# CHIP_dispv1_0.net
KiCad netlist of a schematic drawn in EAGLE
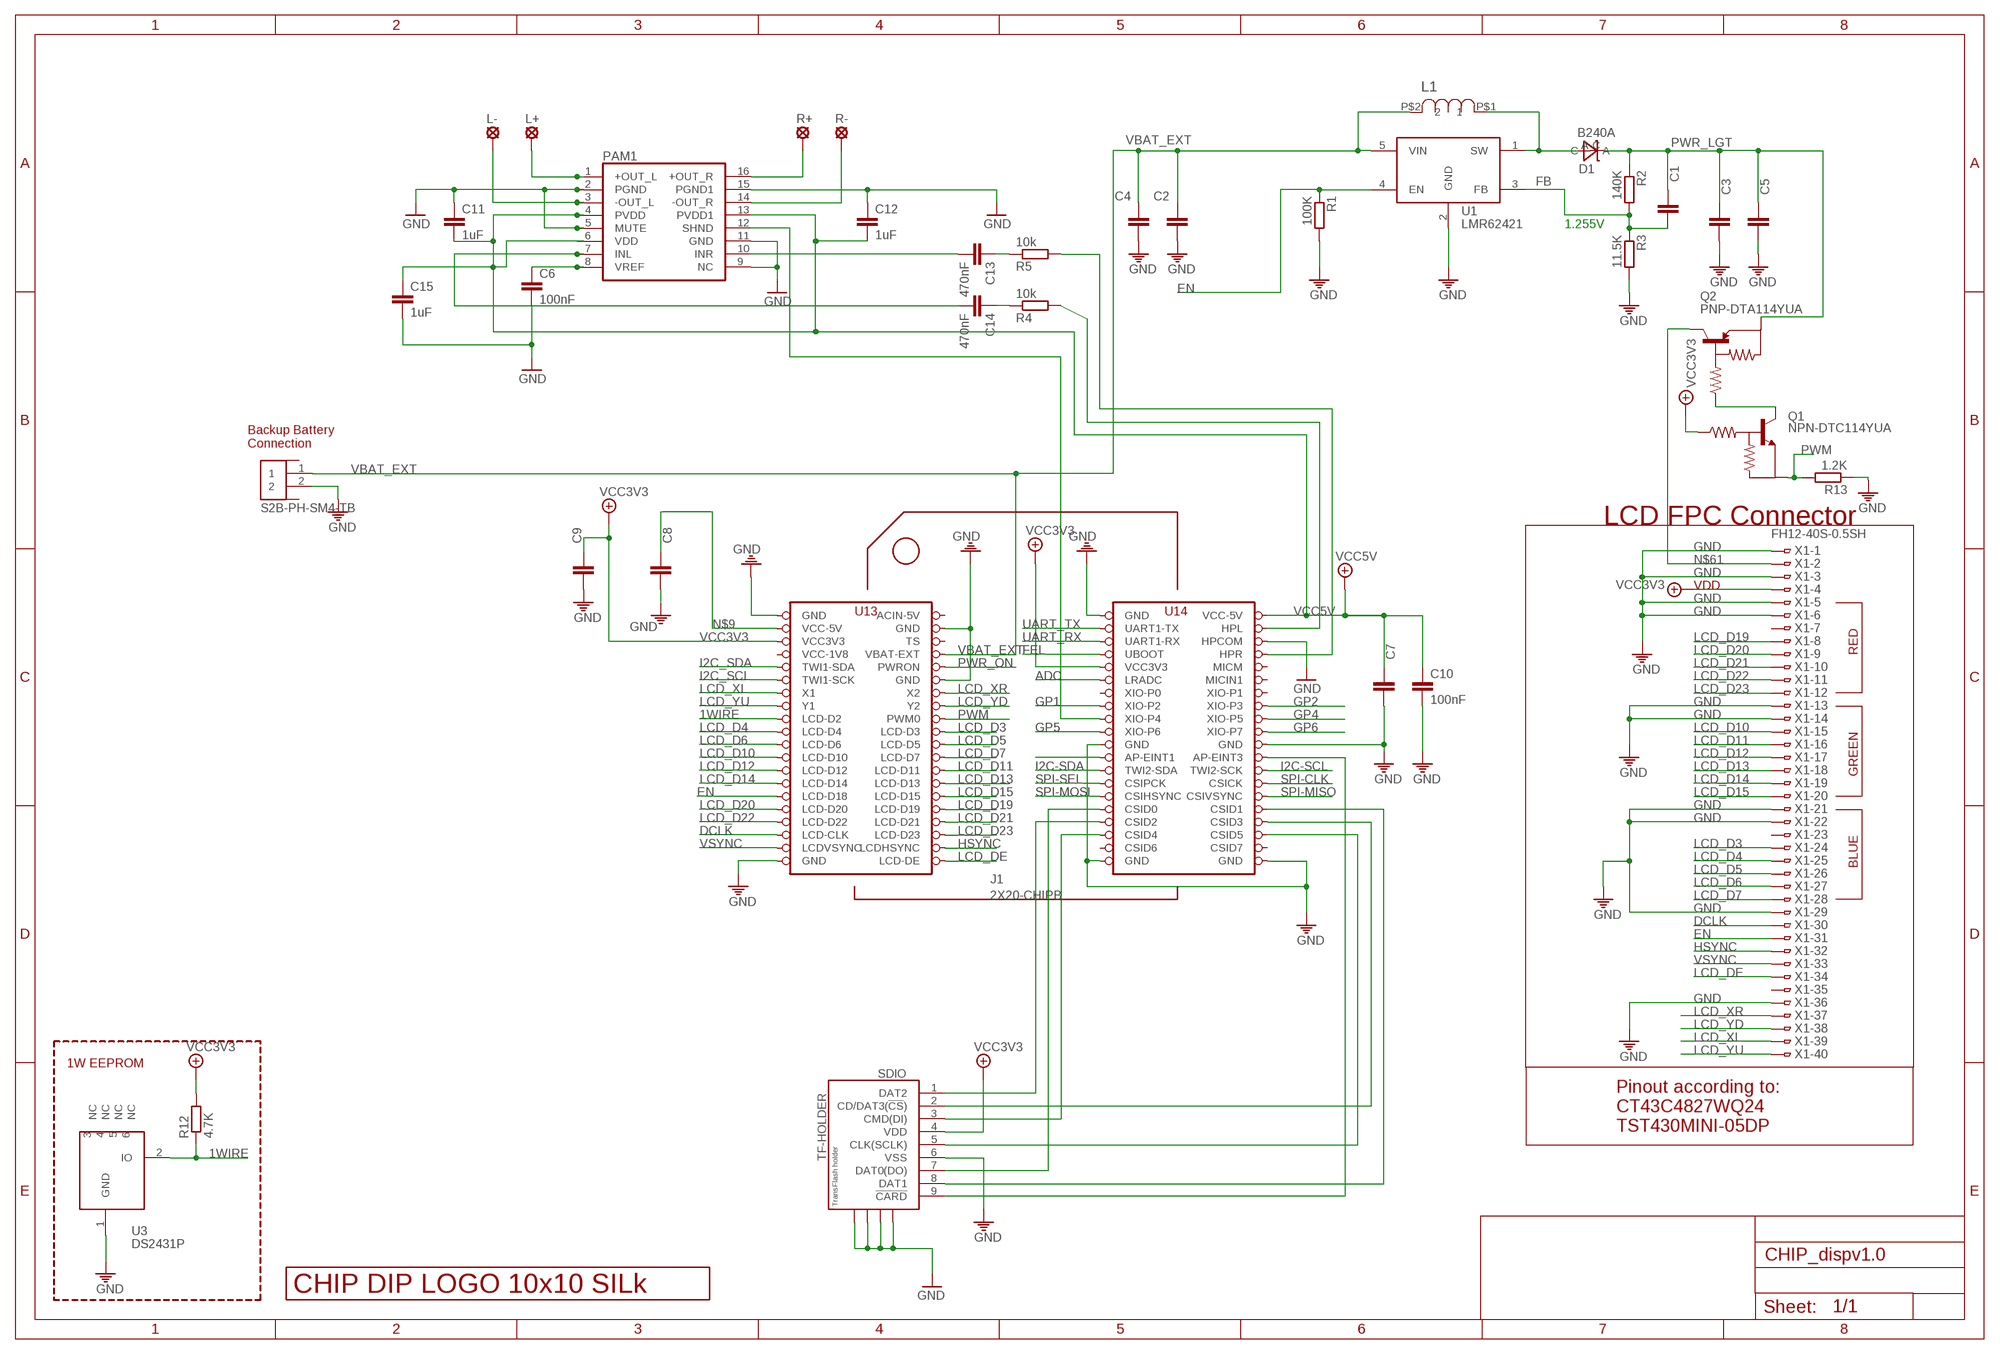
[diagram p0: schematic, sheet 1]

(export (version "E")
  (design (tool "Eeschema 10.0.6"))
  (components
    (comp (ref "C1")
      (value "220pF")
      (footprint "eagle-import:C0805")
      (libsource (lib "eagle-import") (part "C-EUC0805"))
    )
    (comp (ref "C2")
      (value "100nF")
      (footprint "eagle-import:C0805")
      (libsource (lib "eagle-import") (part "C-EUC0805"))
    )
    (comp (ref "C3")
      (value "100nF")
      (footprint "eagle-import:C0805")
      (libsource (lib "eagle-import") (part "C-EUC0805"))
    )
    (comp (ref "C4")
      (value "22uF")
      (footprint "eagle-import:C0805")
      (libsource (lib "eagle-import") (part "C-EUC0805"))
    )
    (comp (ref "C5")
      (value "22uF")
      (footprint "eagle-import:C0805")
      (libsource (lib "eagle-import") (part "C-EUC0805"))
    )
    (comp (ref "C6")
      (value "100nF")
      (footprint "eagle-import:C0805")
      (libsource (lib "eagle-import") (part "C-EUC0805"))
    )
    (comp (ref "C7")
      (value "22uF")
      (footprint "eagle-import:C0805")
      (libsource (lib "eagle-import") (part "C-EUC0805"))
    )
    (comp (ref "C8")
      (value "100nF")
      (footprint "eagle-import:C0805")
      (libsource (lib "eagle-import") (part "C-EUC0805"))
    )
    (comp (ref "C9")
      (value "100nF")
      (footprint "eagle-import:C0805")
      (libsource (lib "eagle-import") (part "C-EUC0805"))
    )
    (comp (ref "C10")
      (value "100nF")
      (footprint "eagle-import:C0805")
      (libsource (lib "eagle-import") (part "C-EUC0805"))
    )
    (comp (ref "C11")
      (value "1uF")
      (footprint "eagle-import:C0805")
      (libsource (lib "eagle-import") (part "C-EUC0805"))
    )
    (comp (ref "C12")
      (value "1uF")
      (footprint "eagle-import:C0805")
      (libsource (lib "eagle-import") (part "C-EUC0805"))
    )
    (comp (ref "C13")
      (value "470nF")
      (footprint "eagle-import:C0805")
      (libsource (lib "eagle-import") (part "C-EUC0805"))
    )
    (comp (ref "C14")
      (value "470nF")
      (footprint "eagle-import:C0805")
      (libsource (lib "eagle-import") (part "C-EUC0805"))
    )
    (comp (ref "C15")
      (value "1uF")
      (footprint "eagle-import:C0805")
      (libsource (lib "eagle-import") (part "C-EUC0805"))
    )
    (comp (ref "D1")
      (value "B240A")
      (footprint "eagle-import:DO-214AC")
      (fields (field (name "MFG") "DIGIKEY") (field (name "VENDOR_PART_NUMBER") "B240A-13-F"))
      (libsource (lib "eagle-import") (part "DIODE_SCHTKY_B240"))
    )
    (comp (ref "J1")
      (value "2X20-CHIPB")
      (footprint "eagle-import:2X20CHIP_SM")
      (libsource (lib "eagle-import") (part "2X20-CHIPB"))
    )
    (comp (ref "J3")
      (value "S2B-PH-SM4-TB")
      (footprint "eagle-import:S2B-PH-SM4-TB")
      (fields (field (name "MFG") "DIGIKEY") (field (name "VENDOR_PART_NUMBER") "S2B-PH-SM4-TB(LF)(SN)"))
      (libsource (lib "eagle-import") (part "S2B-PH-SM4-TB"))
    )
    (comp (ref "L+")
      (value "SE11")
      (footprint "eagle-import:SE11")
      (libsource (lib "eagle-import") (part "SE11"))
    )
    (comp (ref "L-")
      (value "SE11")
      (footprint "eagle-import:SE11")
      (libsource (lib "eagle-import") (part "SE11"))
    )
    (comp (ref "L1")
      (value "SRN6045-100M")
      (footprint "eagle-import:SRN6045")
      (fields (field (name "MFG") "DIGIKEY"))
      (libsource (lib "eagle-import") (part "SRN6045-100M"))
    )
    (comp (ref "PAM1")
      (value "PAM8403")
      (footprint "eagle-import:SOP-16")
      (libsource (lib "eagle-import") (part "PAM8403"))
    )
    (comp (ref "Q1")
      (value "NPN-DTC114YUA")
      (footprint "eagle-import:SOT323")
      (libsource (lib "eagle-import") (part "NPN-DTC114YUA"))
    )
    (comp (ref "Q2")
      (value "PNP-DTA114YUA")
      (footprint "eagle-import:SOT323")
      (libsource (lib "eagle-import") (part "PNP-DTA114YUA"))
    )
    (comp (ref "R+")
      (value "SE11")
      (footprint "eagle-import:SE11")
      (libsource (lib "eagle-import") (part "SE11"))
    )
    (comp (ref "R-")
      (value "SE11")
      (footprint "eagle-import:SE11")
      (libsource (lib "eagle-import") (part "SE11"))
    )
    (comp (ref "R1")
      (value "100K")
      (footprint "eagle-import:M0805")
      (libsource (lib "eagle-import") (part "R-EU_M0805"))
    )
    (comp (ref "R2")
      (value "140K")
      (footprint "eagle-import:M0805")
      (libsource (lib "eagle-import") (part "R-EU_M0805"))
    )
    (comp (ref "R3")
      (value "11.5K")
      (footprint "eagle-import:M0805")
      (libsource (lib "eagle-import") (part "R-EU_M0805"))
    )
    (comp (ref "R4")
      (value "10k")
      (footprint "eagle-import:R0805")
      (libsource (lib "eagle-import") (part "R-EU_R0805"))
    )
    (comp (ref "R5")
      (value "10k")
      (footprint "eagle-import:R0805")
      (libsource (lib "eagle-import") (part "R-EU_R0805"))
    )
    (comp (ref "R12")
      (value "4.7K")
      (footprint "eagle-import:M0805")
      (libsource (lib "eagle-import") (part "R-EU_M0805"))
    )
    (comp (ref "R13")
      (value "1.2K")
      (footprint "eagle-import:M0805")
      (libsource (lib "eagle-import") (part "R-EU_M0805"))
    )
    (comp (ref "SDIO")
      (value "TF-HOLDER")
      (footprint "eagle-import:TF-PULL")
      (libsource (lib "eagle-import") (part "TF-HOLDER"))
    )
    (comp (ref "U$2")
      (value "LOGO_10X10_SILK")
      (footprint "eagle-import:LOGO2_10X10_SILK")
      (libsource (lib "eagle-import") (part "LOGO_10X10_SILK"))
    )
    (comp (ref "U1")
      (value "LMR62421")
      (footprint "eagle-import:SOT23-5")
      (fields (field (name "MFG") "DIGIKEY") (field (name "VENDOR_PART_NUMBER") "LMR62421XMFE/NOPB"))
      (libsource (lib "eagle-import") (part "LMR62421"))
    )
    (comp (ref "U3")
      (value "DS2431P")
      (footprint "eagle-import:TSOC6")
      (fields (field (name "MFG") "DIGIKEY") (field (name "VENDOR_PART_NUMBER") "DS2431P+T&R"))
      (libsource (lib "eagle-import") (part "DS2431P"))
    )
    (comp (ref "X1")
      (value "FH12-40S-0.5SH")
      (footprint "eagle-import:FH12-40S-0.5SH")
      (fields (field (name "MFG") "DIGIKEY") (field (name "VENDOR_PART_NUMBER") "FH12-40S-0.5SH(55)"))
      (libsource (lib "eagle-import") (part "FH12-40S-0.5SH"))
    )
  )
  (nets
    (net (code "1") (name "/1WIRE") (class "Default")
      (node (ref "J1") (pin "LCD-D2") (pinfunction "LCD-D2_LCD-D2") (pintype "passive"))
      (node (ref "R12") (pin "1") (pinfunction "1_1") (pintype "passive"))
      (node (ref "U3") (pin "2") (pinfunction "IO_2") (pintype "bidirectional"))
    )
    (net (code "2") (name "/ADC") (class "Default")
      (node (ref "J1") (pin "LRADC") (pinfunction "LRADC_LRADC") (pintype "passive"))
    )
    (net (code "3") (name "/DCLK") (class "Default")
      (node (ref "J1") (pin "LCD-CLK") (pinfunction "LCD-CLK_LCD-CLK") (pintype "passive"))
      (node (ref "X1") (pin "30") (pinfunction "1_30") (pintype "passive"))
    )
    (net (code "4") (name "/EN") (class "Default")
      (node (ref "J1") (pin "LCD-D18") (pinfunction "LCD-D18_LCD-D18") (pintype "passive"))
      (node (ref "R1") (pin "1") (pinfunction "1_1") (pintype "passive"))
      (node (ref "U1") (pin "4") (pinfunction "EN_4") (pintype "bidirectional"))
      (node (ref "X1") (pin "31") (pinfunction "1_31") (pintype "passive"))
    )
    (net (code "5") (name "/FB") (class "Default")
      (node (ref "C1") (pin "2") (pinfunction "2_2") (pintype "passive"))
      (node (ref "R2") (pin "2") (pinfunction "2_2") (pintype "passive"))
      (node (ref "R3") (pin "1") (pinfunction "1_1") (pintype "passive"))
      (node (ref "U1") (pin "3") (pinfunction "FB_3") (pintype "bidirectional"))
    )
    (net (code "6") (name "/FEL") (class "Default")
      (node (ref "J1") (pin "FEL") (pinfunction "UBOOT_FEL") (pintype "passive"))
    )
    (net (code "7") (name "/GP1") (class "Default")
      (node (ref "J1") (pin "XIO-P2") (pinfunction "XIO-P2_XIO-P2") (pintype "passive"))
    )
    (net (code "8") (name "/GP2") (class "Default")
      (node (ref "J1") (pin "XIO-P3") (pinfunction "XIO-P3_XIO-P3") (pintype "passive"))
    )
    (net (code "9") (name "/GP4") (class "Default")
      (node (ref "J1") (pin "XIO-P5") (pinfunction "XIO-P5_XIO-P5") (pintype "passive"))
    )
    (net (code "10") (name "/GP5") (class "Default")
      (node (ref "J1") (pin "XIO-P6") (pinfunction "XIO-P6_XIO-P6") (pintype "passive"))
    )
    (net (code "11") (name "/GP6") (class "Default")
      (node (ref "J1") (pin "XIO-P7") (pinfunction "XIO-P7_XIO-P7") (pintype "passive"))
    )
    (net (code "12") (name "/HSYNC") (class "Default")
      (node (ref "J1") (pin "LCD-HSYNC") (pinfunction "LCDHSYNC_LCD-HSYNC") (pintype "passive"))
      (node (ref "X1") (pin "32") (pinfunction "1_32") (pintype "passive"))
    )
    (net (code "13") (name "/I2C-SCL") (class "Default")
      (node (ref "J1") (pin "TWI2-SCK") (pinfunction "TWI2-SCK_TWI2-SCK") (pintype "passive"))
    )
    (net (code "14") (name "/I2C-SDA") (class "Default")
      (node (ref "J1") (pin "TWI2-SDA") (pinfunction "TWI2-SDA_TWI2-SDA") (pintype "passive"))
    )
    (net (code "15") (name "/I2C_SCL") (class "Default")
      (node (ref "J1") (pin "TWI1-SCK") (pinfunction "TWI1-SCK_TWI1-SCK") (pintype "passive"))
    )
    (net (code "16") (name "/I2C_SDA") (class "Default")
      (node (ref "J1") (pin "TWI1-SDA") (pinfunction "TWI1-SDA_TWI1-SDA") (pintype "passive"))
    )
    (net (code "17") (name "/LCD_D3") (class "Default")
      (node (ref "J1") (pin "LCD-D3") (pinfunction "LCD-D3_LCD-D3") (pintype "passive"))
      (node (ref "X1") (pin "24") (pinfunction "1_24") (pintype "passive"))
    )
    (net (code "18") (name "/LCD_D4") (class "Default")
      (node (ref "J1") (pin "LCD-D4") (pinfunction "LCD-D4_LCD-D4") (pintype "passive"))
      (node (ref "X1") (pin "25") (pinfunction "1_25") (pintype "passive"))
    )
    (net (code "19") (name "/LCD_D5") (class "Default")
      (node (ref "J1") (pin "LCD-D5") (pinfunction "LCD-D5_LCD-D5") (pintype "passive"))
      (node (ref "X1") (pin "26") (pinfunction "1_26") (pintype "passive"))
    )
    (net (code "20") (name "/LCD_D6") (class "Default")
      (node (ref "J1") (pin "LCD-D6") (pinfunction "LCD-D6_LCD-D6") (pintype "passive"))
      (node (ref "X1") (pin "27") (pinfunction "1_27") (pintype "passive"))
    )
    (net (code "21") (name "/LCD_D7") (class "Default")
      (node (ref "J1") (pin "LCD-D7") (pinfunction "LCD-D7_LCD-D7") (pintype "passive"))
      (node (ref "X1") (pin "28") (pinfunction "1_28") (pintype "passive"))
    )
    (net (code "22") (name "/LCD_D10") (class "Default")
      (node (ref "J1") (pin "LCD-D10") (pinfunction "LCD-D10_LCD-D10") (pintype "passive"))
      (node (ref "X1") (pin "15") (pinfunction "1_15") (pintype "passive"))
    )
    (net (code "23") (name "/LCD_D11") (class "Default")
      (node (ref "J1") (pin "LCD-D11") (pinfunction "LCD-D11_LCD-D11") (pintype "passive"))
      (node (ref "X1") (pin "16") (pinfunction "1_16") (pintype "passive"))
    )
    (net (code "24") (name "/LCD_D12") (class "Default")
      (node (ref "J1") (pin "LCD-D12") (pinfunction "LCD-D12_LCD-D12") (pintype "passive"))
      (node (ref "X1") (pin "17") (pinfunction "1_17") (pintype "passive"))
    )
    (net (code "25") (name "/LCD_D13") (class "Default")
      (node (ref "J1") (pin "LCD-D13") (pinfunction "LCD-D13_LCD-D13") (pintype "passive"))
      (node (ref "X1") (pin "18") (pinfunction "1_18") (pintype "passive"))
    )
    (net (code "26") (name "/LCD_D14") (class "Default")
      (node (ref "J1") (pin "LCD-D14") (pinfunction "LCD-D14_LCD-D14") (pintype "passive"))
      (node (ref "X1") (pin "19") (pinfunction "1_19") (pintype "passive"))
    )
    (net (code "27") (name "/LCD_D15") (class "Default")
      (node (ref "J1") (pin "LCD-D15") (pinfunction "LCD-D15_LCD-D15") (pintype "passive"))
      (node (ref "X1") (pin "20") (pinfunction "1_20") (pintype "passive"))
    )
    (net (code "28") (name "/LCD_D19") (class "Default")
      (node (ref "J1") (pin "LCD-D19") (pinfunction "LCD-D19_LCD-D19") (pintype "passive"))
      (node (ref "X1") (pin "8") (pinfunction "1_8") (pintype "passive"))
    )
    (net (code "29") (name "/LCD_D20") (class "Default")
      (node (ref "J1") (pin "LCD-D20") (pinfunction "LCD-D20_LCD-D20") (pintype "passive"))
      (node (ref "X1") (pin "9") (pinfunction "1_9") (pintype "passive"))
    )
    (net (code "30") (name "/LCD_D21") (class "Default")
      (node (ref "J1") (pin "LCD-D21") (pinfunction "LCD-D21_LCD-D21") (pintype "passive"))
      (node (ref "X1") (pin "10") (pinfunction "1_10") (pintype "passive"))
    )
    (net (code "31") (name "/LCD_D22") (class "Default")
      (node (ref "J1") (pin "LCD-D22") (pinfunction "LCD-D22_LCD-D22") (pintype "passive"))
      (node (ref "X1") (pin "11") (pinfunction "1_11") (pintype "passive"))
    )
    (net (code "32") (name "/LCD_D23") (class "Default")
      (node (ref "J1") (pin "LCD-D23") (pinfunction "LCD-D23_LCD-D23") (pintype "passive"))
      (node (ref "X1") (pin "12") (pinfunction "1_12") (pintype "passive"))
    )
    (net (code "33") (name "/LCD_DE") (class "Default")
      (node (ref "J1") (pin "LCD-DE") (pinfunction "LCD-DE_LCD-DE") (pintype "passive"))
      (node (ref "X1") (pin "34") (pinfunction "1_34") (pintype "passive"))
    )
    (net (code "34") (name "/LCD_XL") (class "Default")
      (node (ref "J1") (pin "X1") (pinfunction "X1_X1") (pintype "passive"))
      (node (ref "X1") (pin "39") (pinfunction "1_39") (pintype "passive"))
    )
    (net (code "35") (name "/LCD_XR") (class "Default")
      (node (ref "J1") (pin "X2") (pinfunction "X2_X2") (pintype "passive"))
      (node (ref "X1") (pin "37") (pinfunction "1_37") (pintype "passive"))
    )
    (net (code "36") (name "/LCD_YD") (class "Default")
      (node (ref "J1") (pin "Y2") (pinfunction "Y2_Y2") (pintype "passive"))
      (node (ref "X1") (pin "38") (pinfunction "1_38") (pintype "passive"))
    )
    (net (code "37") (name "/LCD_YU") (class "Default")
      (node (ref "J1") (pin "Y1") (pinfunction "Y1_Y1") (pintype "passive"))
      (node (ref "X1") (pin "40") (pinfunction "1_40") (pintype "passive"))
    )
    (net (code "38") (name "/N$9") (class "Default")
      (node (ref "C8") (pin "1") (pinfunction "1_1") (pintype "passive"))
      (node (ref "J1") (pin "VCC5V@0") (pinfunction "VCC-5V_VCC5V@0") (pintype "power_in"))
    )
    (net (code "39") (name "/N$61") (class "Default")
      (node (ref "Q2") (pin "3") (pinfunction "OUT_3") (pintype "passive"))
      (node (ref "X1") (pin "2") (pinfunction "1_2") (pintype "passive"))
    )
    (net (code "40") (name "/PWM") (class "Default")
      (node (ref "J1") (pin "PWM0") (pinfunction "PWM0_PWM0") (pintype "passive"))
      (node (ref "Q1") (pin "2") (pinfunction "GND_2") (pintype "passive"))
      (node (ref "R13") (pin "2") (pinfunction "2_2") (pintype "passive"))
    )
    (net (code "41") (name "/PWR_LGT") (class "Default")
      (node (ref "C1") (pin "1") (pinfunction "1_1") (pintype "passive"))
      (node (ref "C3") (pin "1") (pinfunction "1_1") (pintype "passive"))
      (node (ref "C5") (pin "1") (pinfunction "1_1") (pintype "passive"))
      (node (ref "D1") (pin "C") (pinfunction "C_C") (pintype "bidirectional"))
      (node (ref "Q2") (pin "2") (pinfunction "GND_2") (pintype "passive"))
      (node (ref "R2") (pin "1") (pinfunction "1_1") (pintype "passive"))
    )
    (net (code "42") (name "/PWR_ON") (class "Default")
      (node (ref "J1") (pin "PWRON") (pinfunction "PWRON_PWRON") (pintype "passive"))
    )
    (net (code "43") (name "/SPI-CLK") (class "Default")
      (node (ref "J1") (pin "CSICK") (pinfunction "CSICK_CSICK") (pintype "passive"))
    )
    (net (code "44") (name "/SPI-MISO") (class "Default")
      (node (ref "J1") (pin "CSIVSYNC") (pinfunction "CSIVSYNC_CSIVSYNC") (pintype "passive"))
    )
    (net (code "45") (name "/SPI-MOSI") (class "Default")
      (node (ref "J1") (pin "CSIHSYNC") (pinfunction "CSIHSYNC_CSIHSYNC") (pintype "passive"))
    )
    (net (code "46") (name "/SPI-SEL") (class "Default")
      (node (ref "J1") (pin "CSIPCK") (pinfunction "CSIPCK_CSIPCK") (pintype "passive"))
    )
    (net (code "47") (name "/UART_RX") (class "Default")
      (node (ref "J1") (pin "UART1-RX") (pinfunction "UART1-RX_UART1-RX") (pintype "passive"))
    )
    (net (code "48") (name "/UART_TX") (class "Default")
      (node (ref "J1") (pin "UART1-TX") (pinfunction "UART1-TX_UART1-TX") (pintype "passive"))
    )
    (net (code "49") (name "/VBAT_EXT") (class "Default")
      (node (ref "C2") (pin "1") (pinfunction "1_1") (pintype "passive"))
      (node (ref "C4") (pin "1") (pinfunction "1_1") (pintype "passive"))
      (node (ref "J1") (pin "BAT") (pinfunction "VBAT-EXT_BAT") (pintype "passive"))
      (node (ref "J3") (pin "1") (pinfunction "1_1") (pintype "bidirectional"))
      (node (ref "L1") (pin "P$2") (pinfunction "2_P$2") (pintype "passive"))
      (node (ref "U1") (pin "5") (pinfunction "VIN_5") (pintype "bidirectional"))
    )
    (net (code "50") (name "/VCC-1V8") (class "Default")
      (node (ref "J1") (pin "VCC1V8") (pinfunction "VCC-1V8_VCC1V8") (pintype "power_in"))
    )
    (net (code "51") (name "/VSYNC") (class "Default")
      (node (ref "J1") (pin "LCD-VSYNC") (pinfunction "LCDVSYNC_LCD-VSYNC") (pintype "passive"))
      (node (ref "X1") (pin "33") (pinfunction "1_33") (pintype "passive"))
    )
    (net (code "52") (name "GND") (class "Default")
      (node (ref "C10") (pin "2") (pinfunction "2_2") (pintype "passive"))
      (node (ref "C11") (pin "1") (pinfunction "1_1") (pintype "passive"))
      (node (ref "C12") (pin "1") (pinfunction "1_1") (pintype "passive"))
      (node (ref "C15") (pin "2") (pinfunction "2_2") (pintype "passive"))
      (node (ref "C2") (pin "2") (pinfunction "2_2") (pintype "passive"))
      (node (ref "C3") (pin "2") (pinfunction "2_2") (pintype "passive"))
      (node (ref "C4") (pin "2") (pinfunction "2_2") (pintype "passive"))
      (node (ref "C5") (pin "2") (pinfunction "2_2") (pintype "passive"))
      (node (ref "C6") (pin "2") (pinfunction "2_2") (pintype "passive"))
      (node (ref "C7") (pin "2") (pinfunction "2_2") (pintype "passive"))
      (node (ref "C8") (pin "2") (pinfunction "2_2") (pintype "passive"))
      (node (ref "C9") (pin "2") (pinfunction "2_2") (pintype "passive"))
      (node (ref "J1") (pin "GND@1") (pinfunction "GND_GND@1") (pintype "power_in"))
      (node (ref "J1") (pin "GND@10") (pinfunction "GND_GND@10") (pintype "power_in"))
      (node (ref "J1") (pin "GND@2") (pinfunction "GND_GND@2") (pintype "power_in"))
      (node (ref "J1") (pin "GND@3") (pinfunction "GND_GND@3") (pintype "power_in"))
      (node (ref "J1") (pin "GND@4") (pinfunction "GND_GND@4") (pintype "power_in"))
      (node (ref "J1") (pin "GND@5") (pinfunction "GND_GND@5") (pintype "power_in"))
      (node (ref "J1") (pin "GND@6") (pinfunction "GND_GND@6") (pintype "power_in"))
      (node (ref "J1") (pin "GND@7") (pinfunction "GND_GND@7") (pintype "power_in"))
      (node (ref "J1") (pin "GND@8") (pinfunction "GND_GND@8") (pintype "power_in"))
      (node (ref "J1") (pin "HPCOM") (pinfunction "HPCOM_HPCOM") (pintype "passive"))
      (node (ref "J3") (pin "2") (pinfunction "2_2") (pintype "bidirectional"))
      (node (ref "PAM1") (pin "11") (pinfunction "GND_11") (pintype "output"))
      (node (ref "PAM1") (pin "15") (pinfunction "PGND1_15") (pintype "output"))
      (node (ref "PAM1") (pin "2") (pinfunction "PGND_2") (pintype "input"))
      (node (ref "PAM1") (pin "5") (pinfunction "MUTE_5") (pintype "input"))
      (node (ref "PAM1") (pin "9") (pinfunction "NC_9") (pintype "output"))
      (node (ref "R1") (pin "2") (pinfunction "2_2") (pintype "passive"))
      (node (ref "R13") (pin "1") (pinfunction "1_1") (pintype "passive"))
      (node (ref "R3") (pin "2") (pinfunction "2_2") (pintype "passive"))
      (node (ref "SDIO") (pin "6") (pinfunction "VSS_6") (pintype "power_in"))
      (node (ref "SDIO") (pin "S1") (pinfunction "S1_S1") (pintype "passive"))
      (node (ref "SDIO") (pin "S2") (pinfunction "S2_S2") (pintype "passive"))
      (node (ref "SDIO") (pin "S3") (pinfunction "S3_S3") (pintype "passive"))
      (node (ref "SDIO") (pin "S4") (pinfunction "S4_S4") (pintype "passive"))
      (node (ref "U1") (pin "2") (pinfunction "GND_2") (pintype "bidirectional"))
      (node (ref "U3") (pin "1") (pinfunction "GND_1") (pintype "bidirectional"))
      (node (ref "X1") (pin "1") (pinfunction "1_1") (pintype "passive"))
      (node (ref "X1") (pin "13") (pinfunction "1_13") (pintype "passive"))
      (node (ref "X1") (pin "14") (pinfunction "1_14") (pintype "passive"))
      (node (ref "X1") (pin "21") (pinfunction "1_21") (pintype "passive"))
      (node (ref "X1") (pin "22") (pinfunction "1_22") (pintype "passive"))
      (node (ref "X1") (pin "29") (pinfunction "1_29") (pintype "passive"))
      (node (ref "X1") (pin "3") (pinfunction "1_3") (pintype "passive"))
      (node (ref "X1") (pin "36") (pinfunction "1_36") (pintype "passive"))
      (node (ref "X1") (pin "5") (pinfunction "1_5") (pintype "passive"))
      (node (ref "X1") (pin "6") (pinfunction "1_6") (pintype "passive"))
    )
    (net (code "53") (name "Net-(C13-Pad1)") (class "Default")
      (node (ref "C13") (pin "1") (pinfunction "1_1") (pintype "passive"))
      (node (ref "R5") (pin "1") (pinfunction "1_1") (pintype "passive"))
    )
    (net (code "54") (name "Net-(C14-Pad1)") (class "Default")
      (node (ref "C14") (pin "1") (pinfunction "1_1") (pintype "passive"))
      (node (ref "R4") (pin "1") (pinfunction "1_1") (pintype "passive"))
    )
    (net (code "55") (name "Net-(J1-PadHPL)") (class "Default")
      (node (ref "J1") (pin "HPL") (pinfunction "HPL_HPL") (pintype "passive"))
      (node (ref "R4") (pin "2") (pinfunction "2_2") (pintype "passive"))
    )
    (net (code "56") (name "Net-(J1-PadHPR)") (class "Default")
      (node (ref "J1") (pin "HPR") (pinfunction "HPR_HPR") (pintype "passive"))
      (node (ref "R5") (pin "2") (pinfunction "2_2") (pintype "passive"))
    )
    (net (code "57") (name "Net-(L1-1)") (class "Default")
      (node (ref "D1") (pin "A") (pinfunction "A_A") (pintype "bidirectional"))
      (node (ref "L1") (pin "P$1") (pinfunction "1_P$1") (pintype "passive"))
      (node (ref "U1") (pin "1") (pinfunction "SW_1") (pintype "bidirectional"))
    )
    (net (code "58") (name "Net-(PAM1-+OUT_L)") (class "Default")
      (node (ref "L+") (pin "MP") (pinfunction "MP_MP") (pintype "passive"))
      (node (ref "PAM1") (pin "1") (pinfunction "+OUT_L_1") (pintype "input"))
    )
    (net (code "59") (name "Net-(PAM1-+OUT_R)") (class "Default")
      (node (ref "PAM1") (pin "16") (pinfunction "+OUT_R_16") (pintype "output"))
      (node (ref "R+") (pin "MP") (pinfunction "MP_MP") (pintype "passive"))
    )
    (net (code "60") (name "Net-(PAM1--OUT_L)") (class "Default")
      (node (ref "L-") (pin "MP") (pinfunction "MP_MP") (pintype "passive"))
      (node (ref "PAM1") (pin "3") (pinfunction "-OUT_L_3") (pintype "input"))
    )
    (net (code "61") (name "Net-(PAM1--OUT_R)") (class "Default")
      (node (ref "PAM1") (pin "14") (pinfunction "-OUT_R_14") (pintype "output"))
      (node (ref "R-") (pin "MP") (pinfunction "MP_MP") (pintype "passive"))
    )
    (net (code "62") (name "Net-(PAM1-INL)") (class "Default")
      (node (ref "C14") (pin "2") (pinfunction "2_2") (pintype "passive"))
      (node (ref "PAM1") (pin "7") (pinfunction "INL_7") (pintype "input"))
    )
    (net (code "63") (name "Net-(PAM1-INR)") (class "Default")
      (node (ref "C13") (pin "2") (pinfunction "2_2") (pintype "passive"))
      (node (ref "PAM1") (pin "10") (pinfunction "INR_10") (pintype "output"))
    )
    (net (code "64") (name "Net-(PAM1-SHND)") (class "Default")
      (node (ref "J1") (pin "XIO-P4") (pinfunction "XIO-P4_XIO-P4") (pintype "passive"))
      (node (ref "PAM1") (pin "12") (pinfunction "SHND_12") (pintype "output"))
    )
    (net (code "65") (name "Net-(PAM1-VREF)") (class "Default")
      (node (ref "C6") (pin "1") (pinfunction "1_1") (pintype "passive"))
      (node (ref "PAM1") (pin "8") (pinfunction "VREF_8") (pintype "input"))
    )
    (net (code "66") (name "Net-(Q1-OUT)") (class "Default")
      (node (ref "Q1") (pin "3") (pinfunction "OUT_3") (pintype "passive"))
      (node (ref "Q2") (pin "1") (pinfunction "IN_1") (pintype "passive"))
    )
    (net (code "67") (name "Net-(SDIO-CD{slash}DAT3(~{CS}))") (class "Default")
      (node (ref "J1") (pin "CSID3") (pinfunction "CSID3_CSID3") (pintype "passive"))
      (node (ref "SDIO") (pin "2") (pinfunction "CD/DAT3(~{CS})_2") (pintype "bidirectional"))
    )
    (net (code "68") (name "Net-(SDIO-CLK(SCLK))") (class "Default")
      (node (ref "J1") (pin "CSID5") (pinfunction "CSID5_CSID5") (pintype "passive"))
      (node (ref "SDIO") (pin "5") (pinfunction "CLK(SCLK)_5") (pintype "input"))
    )
    (net (code "69") (name "Net-(SDIO-CMD(DI))") (class "Default")
      (node (ref "J1") (pin "CSID4") (pinfunction "CSID4_CSID4") (pintype "passive"))
      (node (ref "SDIO") (pin "3") (pinfunction "CMD(DI)_3") (pintype "bidirectional"))
    )
    (net (code "70") (name "Net-(SDIO-DAT0(DO))") (class "Default")
      (node (ref "J1") (pin "CSID0") (pinfunction "CSID0_CSID0") (pintype "passive"))
      (node (ref "SDIO") (pin "7") (pinfunction "DAT0(DO)_7") (pintype "bidirectional"))
    )
    (net (code "71") (name "Net-(SDIO-DAT1)") (class "Default")
      (node (ref "J1") (pin "CSID1") (pinfunction "CSID1_CSID1") (pintype "passive"))
      (node (ref "SDIO") (pin "8") (pinfunction "DAT1_8") (pintype "bidirectional"))
    )
    (net (code "72") (name "Net-(SDIO-DAT2)") (class "Default")
      (node (ref "J1") (pin "CSID2") (pinfunction "CSID2_CSID2") (pintype "passive"))
      (node (ref "SDIO") (pin "1") (pinfunction "DAT2_1") (pintype "bidirectional"))
    )
    (net (code "73") (name "Net-(SDIO-~{CARD})") (class "Default")
      (node (ref "J1") (pin "AP-EINT3") (pinfunction "AP-EINT3_AP-EINT3") (pintype "passive"))
      (node (ref "SDIO") (pin "9") (pinfunction "~{CARD}_9") (pintype "passive"))
    )
    (net (code "74") (name "VCC3V3") (class "Default")
      (node (ref "C9") (pin "1") (pinfunction "1_1") (pintype "passive"))
      (node (ref "J1") (pin "VCC3V3") (pinfunction "VCC3V3_VCC3V3") (pintype "power_in"))
      (node (ref "J1") (pin "VCC3V3@1") (pinfunction "VCC3V3_VCC3V3@1") (pintype "power_in"))
      (node (ref "Q1") (pin "1") (pinfunction "IN_1") (pintype "passive"))
      (node (ref "R12") (pin "2") (pinfunction "2_2") (pintype "passive"))
      (node (ref "SDIO") (pin "4") (pinfunction "VDD_4") (pintype "power_in"))
      (node (ref "X1") (pin "4") (pinfunction "1_4") (pintype "passive"))
    )
    (net (code "75") (name "VCC5V") (class "Default")
      (node (ref "C10") (pin "1") (pinfunction "1_1") (pintype "passive"))
      (node (ref "C11") (pin "2") (pinfunction "2_2") (pintype "passive"))
      (node (ref "C12") (pin "2") (pinfunction "2_2") (pintype "passive"))
      (node (ref "C15") (pin "1") (pinfunction "1_1") (pintype "passive"))
      (node (ref "C7") (pin "1") (pinfunction "1_1") (pintype "passive"))
      (node (ref "J1") (pin "VCC5V@1") (pinfunction "VCC-5V_VCC5V@1") (pintype "power_in"))
      (node (ref "PAM1") (pin "13") (pinfunction "PVDD1_13") (pintype "output"))
      (node (ref "PAM1") (pin "4") (pinfunction "PVDD_4") (pintype "input"))
      (node (ref "PAM1") (pin "6") (pinfunction "VDD_6") (pintype "input"))
    )
    (net (code "76") (name "unconnected-(J1-ACIN-5V-PadCHG-IN)") (class "Default")
      (node (ref "J1") (pin "CHG-IN") (pinfunction "ACIN-5V_CHG-IN") (pintype "passive"))
    )
    (net (code "77") (name "unconnected-(J1-PadAP-EINT1)") (class "Default")
      (node (ref "J1") (pin "AP-EINT1") (pinfunction "AP-EINT1_AP-EINT1") (pintype "passive"))
    )
    (net (code "78") (name "unconnected-(J1-PadCSID6)") (class "Default")
      (node (ref "J1") (pin "CSID6") (pinfunction "CSID6_CSID6") (pintype "passive"))
    )
    (net (code "79") (name "unconnected-(J1-PadCSID7)") (class "Default")
      (node (ref "J1") (pin "CSID7") (pinfunction "CSID7_CSID7") (pintype "passive"))
    )
    (net (code "80") (name "unconnected-(J1-PadMICIN1)") (class "Default")
      (node (ref "J1") (pin "MICIN1") (pinfunction "MICIN1_MICIN1") (pintype "passive"))
    )
    (net (code "81") (name "unconnected-(J1-PadMICM)") (class "Default")
      (node (ref "J1") (pin "MICM") (pinfunction "MICM_MICM") (pintype "passive"))
    )
    (net (code "82") (name "unconnected-(J1-PadTS)") (class "Default")
      (node (ref "J1") (pin "TS") (pinfunction "TS_TS") (pintype "passive"))
    )
    (net (code "83") (name "unconnected-(J1-PadXIO-P0)") (class "Default")
      (node (ref "J1") (pin "XIO-P0") (pinfunction "XIO-P0_XIO-P0") (pintype "passive"))
    )
    (net (code "84") (name "unconnected-(J1-PadXIO-P1)") (class "Default")
      (node (ref "J1") (pin "XIO-P1") (pinfunction "XIO-P1_XIO-P1") (pintype "passive"))
    )
    (net (code "85") (name "unconnected-(J3-PadMNT1)") (class "Default")
      (node (ref "J3") (pin "MNT1") (pinfunction "MNT1_MNT1") (pintype "no_connect"))
    )
    (net (code "86") (name "unconnected-(J3-PadMNT2)") (class "Default")
      (node (ref "J3") (pin "MNT2") (pinfunction "MNT2_MNT2") (pintype "no_connect"))
    )
    (net (code "87") (name "unconnected-(U3-NC-Pad3)") (class "Default")
      (node (ref "U3") (pin "3") (pinfunction "NC_3") (pintype "bidirectional"))
    )
    (net (code "88") (name "unconnected-(U3-NC-Pad4)") (class "Default")
      (node (ref "U3") (pin "4") (pinfunction "NC_4") (pintype "bidirectional"))
    )
    (net (code "89") (name "unconnected-(U3-NC-Pad5)") (class "Default")
      (node (ref "U3") (pin "5") (pinfunction "NC_5") (pintype "bidirectional"))
    )
    (net (code "90") (name "unconnected-(U3-NC-Pad6)") (class "Default")
      (node (ref "U3") (pin "6") (pinfunction "NC_6") (pintype "bidirectional"))
    )
    (net (code "91") (name "unconnected-(X1AC-1-Pad35)") (class "Default")
      (node (ref "X1") (pin "35") (pinfunction "1_35") (pintype "passive"))
    )
    (net (code "92") (name "unconnected-(X1AL-1-Pad7)") (class "Default")
      (node (ref "X1") (pin "7") (pinfunction "1_7") (pintype "passive"))
    )
    (net (code "93") (name "unconnected-(X1P-1-Pad23)") (class "Default")
      (node (ref "X1") (pin "23") (pinfunction "1_23") (pintype "passive"))
    )
  )
)
